# ZATINO_2020.net
KiCad netlist of a schematic drawn in EAGLE
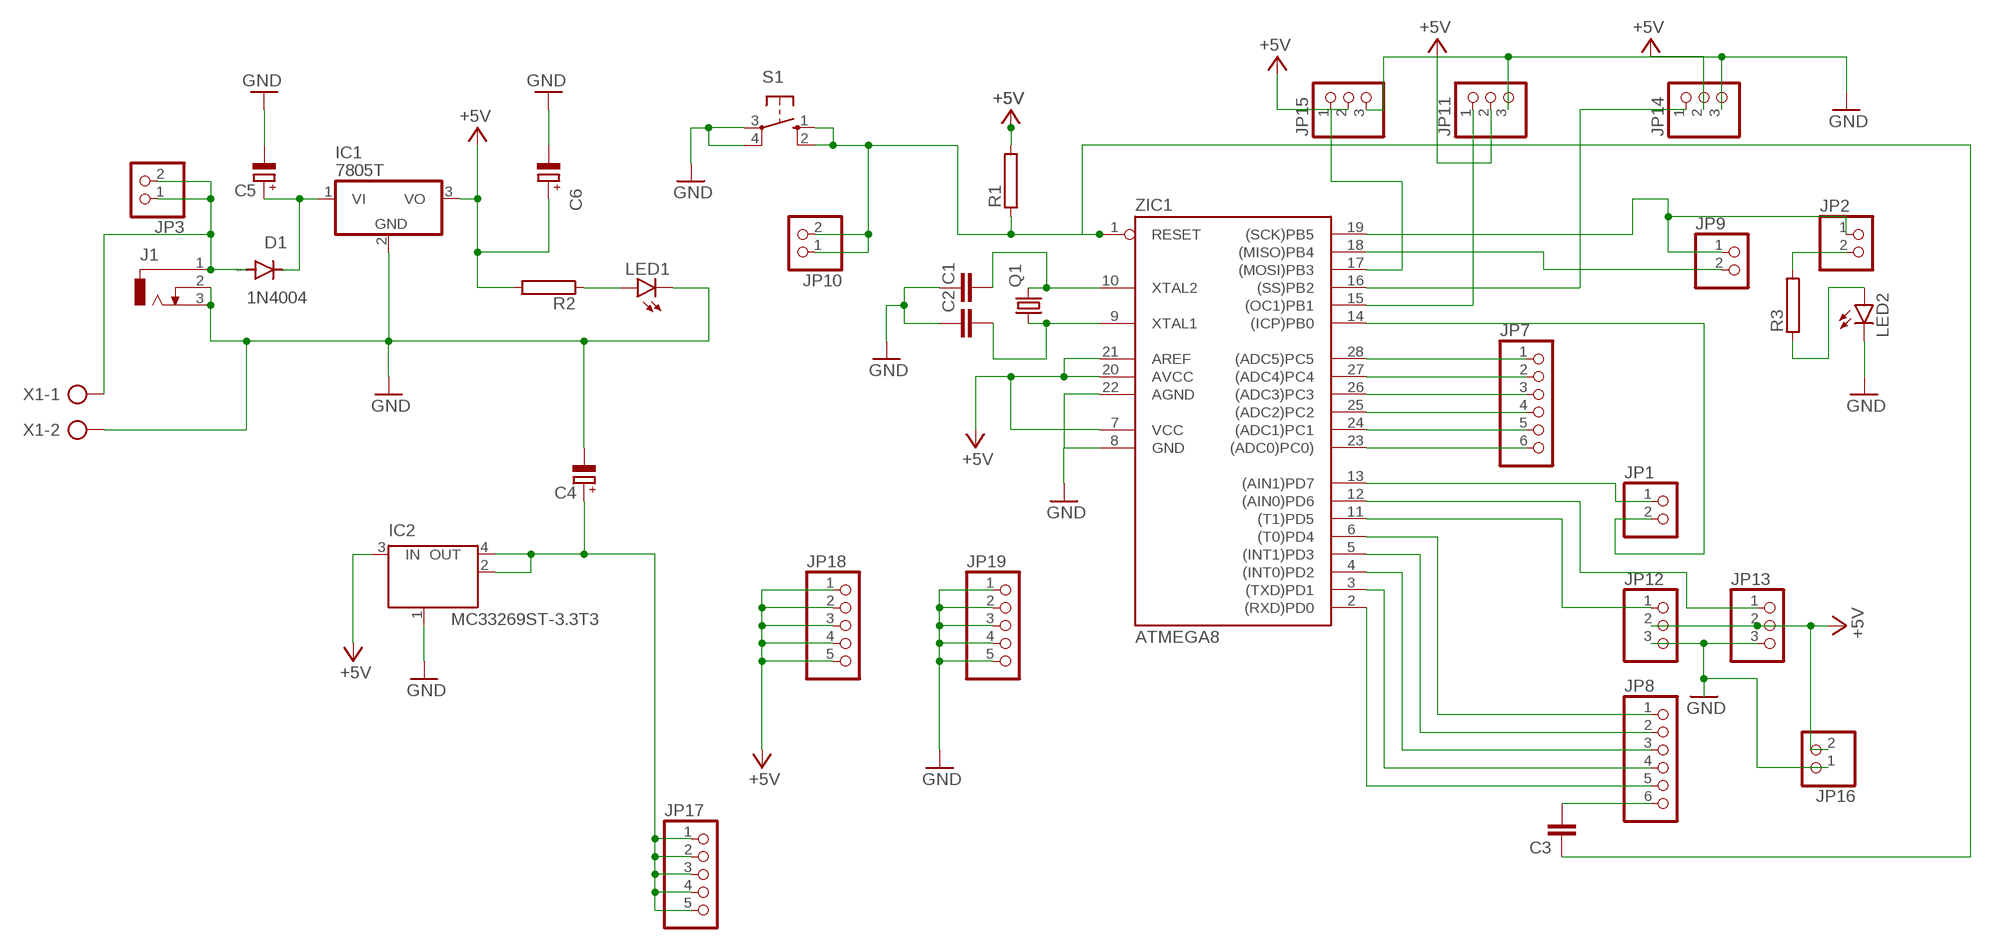
[diagram p0: schematic, sheet 1]

(export (version "E")
  (design (tool "Eeschema 10.0.6"))
  (components
    (comp (ref "C1")
      (value "C2.5/2")
      (footprint "eagle-import:C2.5-2")
      (libsource (lib "eagle-import") (part "C2.5/2"))
    )
    (comp (ref "C2")
      (value "C2.5/2")
      (footprint "eagle-import:C2.5-2")
      (libsource (lib "eagle-import") (part "C2.5/2"))
    )
    (comp (ref "C3")
      (value "C2,5-3")
      (footprint "eagle-import:C2.5-3")
      (libsource (lib "eagle-import") (part "C2,5-3"))
    )
    (comp (ref "C4")
      (value "CPOL-EUE2,5-6E")
      (footprint "eagle-import:E2,5-6E")
      (libsource (lib "eagle-import") (part "CPOL-EUE2,5-6E"))
    )
    (comp (ref "C5")
      (value "CPOL-EUE2,5-6E")
      (footprint "eagle-import:E2,5-6E")
      (libsource (lib "eagle-import") (part "CPOL-EUE2,5-6E"))
    )
    (comp (ref "C6")
      (value "CPOL-EUE2,5-6E")
      (footprint "eagle-import:E2,5-6E")
      (libsource (lib "eagle-import") (part "CPOL-EUE2,5-6E"))
    )
    (comp (ref "D1")
      (value "1N4004")
      (footprint "eagle-import:DO41-10")
      (libsource (lib "eagle-import") (part "1N4004"))
    )
    (comp (ref "IC1")
      (value "7805T")
      (footprint "eagle-import:TO220H")
      (libsource (lib "eagle-import") (part "78T05"))
    )
    (comp (ref "IC2")
      (value "MC33269ST-3.3T3")
      (footprint "eagle-import:SOT223")
      (libsource (lib "eagle-import") (part "MC33269ST-3.3T3"))
    )
    (comp (ref "J1")
      (value "DCJ0303")
      (footprint "eagle-import:DCJ0303")
      (libsource (lib "eagle-import") (part "DCJ0303"))
    )
    (comp (ref "JP1")
      (value "PINHD-1X2")
      (footprint "eagle-import:1X02")
      (libsource (lib "eagle-import") (part "PINHD-1X2"))
    )
    (comp (ref "JP2")
      (value "PINHD-1X2")
      (footprint "eagle-import:1X02")
      (libsource (lib "eagle-import") (part "PINHD-1X2"))
    )
    (comp (ref "JP3")
      (value "PINHD-1X2")
      (footprint "eagle-import:1X02")
      (libsource (lib "eagle-import") (part "PINHD-1X2"))
    )
    (comp (ref "JP7")
      (value "PINHD-1X6")
      (footprint "eagle-import:1X06")
      (libsource (lib "eagle-import") (part "PINHD-1X6"))
    )
    (comp (ref "JP8")
      (value "PINHD-1X6")
      (footprint "eagle-import:1X06")
      (libsource (lib "eagle-import") (part "PINHD-1X6"))
    )
    (comp (ref "JP9")
      (value "PINHD-1X2")
      (footprint "eagle-import:1X02")
      (libsource (lib "eagle-import") (part "PINHD-1X2"))
    )
    (comp (ref "JP10")
      (value "PINHD-1X2")
      (footprint "eagle-import:1X02")
      (libsource (lib "eagle-import") (part "PINHD-1X2"))
    )
    (comp (ref "JP11")
      (value "PINHD-1X3")
      (footprint "eagle-import:1X03")
      (libsource (lib "eagle-import") (part "PINHD-1X3"))
    )
    (comp (ref "JP12")
      (value "PINHD-1X3")
      (footprint "eagle-import:1X03")
      (libsource (lib "eagle-import") (part "PINHD-1X3"))
    )
    (comp (ref "JP13")
      (value "PINHD-1X3")
      (footprint "eagle-import:1X03")
      (libsource (lib "eagle-import") (part "PINHD-1X3"))
    )
    (comp (ref "JP14")
      (value "PINHD-1X3")
      (footprint "eagle-import:1X03")
      (libsource (lib "eagle-import") (part "PINHD-1X3"))
    )
    (comp (ref "JP15")
      (value "PINHD-1X3")
      (footprint "eagle-import:1X03")
      (libsource (lib "eagle-import") (part "PINHD-1X3"))
    )
    (comp (ref "JP16")
      (value "PINHD-1X2")
      (footprint "eagle-import:1X02")
      (libsource (lib "eagle-import") (part "PINHD-1X2"))
    )
    (comp (ref "JP17")
      (value "PINHD-1X5")
      (footprint "eagle-import:1X05")
      (libsource (lib "eagle-import") (part "PINHD-1X5"))
    )
    (comp (ref "JP18")
      (value "PINHD-1X5")
      (footprint "eagle-import:1X05")
      (libsource (lib "eagle-import") (part "PINHD-1X5"))
    )
    (comp (ref "JP19")
      (value "PINHD-1X5")
      (footprint "eagle-import:1X05")
      (libsource (lib "eagle-import") (part "PINHD-1X5"))
    )
    (comp (ref "LED1")
      (value "LED5MM")
      (footprint "eagle-import:LED5MM")
      (libsource (lib "eagle-import") (part "LED5MM"))
    )
    (comp (ref "LED2")
      (value "LED5MM")
      (footprint "eagle-import:LED5MM")
      (libsource (lib "eagle-import") (part "LED5MM"))
    )
    (comp (ref "Q1")
      (value "CRYSTALHC49U-V")
      (footprint "eagle-import:HC49U-V")
      (libsource (lib "eagle-import") (part "CRYSTALHC49U-V"))
    )
    (comp (ref "R1")
      (value "RRS1/4")
      (footprint "eagle-import:RS1_4")
      (fields (field (name "MF") "OHMITE") (field (name "MPN") "RRS1K0"))
      (libsource (lib "eagle-import") (part "RRS1/4"))
    )
    (comp (ref "R2")
      (value "RRS1/4")
      (footprint "eagle-import:RS1_4")
      (fields (field (name "MF") "OHMITE") (field (name "MPN") "RRS1K0"))
      (libsource (lib "eagle-import") (part "RRS1/4"))
    )
    (comp (ref "R3")
      (value "RRS1/4")
      (footprint "eagle-import:RS1_4")
      (fields (field (name "MF") "OHMITE") (field (name "MPN") "RRS1K0"))
      (libsource (lib "eagle-import") (part "RRS1/4"))
    )
    (comp (ref "S1")
      (value "10-XX")
      (footprint "eagle-import:B3F-10XX")
      (fields (field (name "MPN") "B3F-1000"))
      (libsource (lib "eagle-import") (part "10-XX"))
    )
    (comp (ref "X1")
      (value "AK300/2")
      (footprint "eagle-import:AK300_2")
      (libsource (lib "eagle-import") (part "AK300/2"))
    )
    (comp (ref "ZIC1")
      (value "ATMEGA8")
      (footprint "eagle-import:DIL28-3")
      (libsource (lib "eagle-import") (part "AT90S4433P"))
    )
  )
  (nets
    (net (code "1") (name "+5V") (class "Default")
      (node (ref "C6") (pin "+") (pinfunction "+_+") (pintype "passive"))
      (node (ref "IC1") (pin "3") (pinfunction "VO_3") (pintype "passive"))
      (node (ref "IC2") (pin "3") (pinfunction "IN_3") (pintype "input"))
      (node (ref "JP11") (pin "2") (pinfunction "2_2") (pintype "passive"))
      (node (ref "JP12") (pin "2") (pinfunction "2_2") (pintype "passive"))
      (node (ref "JP13") (pin "2") (pinfunction "2_2") (pintype "passive"))
      (node (ref "JP14") (pin "2") (pinfunction "2_2") (pintype "passive"))
      (node (ref "JP15") (pin "2") (pinfunction "2_2") (pintype "passive"))
      (node (ref "JP16") (pin "2") (pinfunction "2_2") (pintype "passive"))
      (node (ref "JP18") (pin "1") (pinfunction "1_1") (pintype "passive"))
      (node (ref "JP18") (pin "2") (pinfunction "2_2") (pintype "passive"))
      (node (ref "JP18") (pin "3") (pinfunction "3_3") (pintype "passive"))
      (node (ref "JP18") (pin "4") (pinfunction "4_4") (pintype "passive"))
      (node (ref "JP18") (pin "5") (pinfunction "5_5") (pintype "passive"))
      (node (ref "R1") (pin "2") (pinfunction "2_2") (pintype "passive"))
      (node (ref "R2") (pin "2") (pinfunction "2_2") (pintype "passive"))
      (node (ref "ZIC1") (pin "20") (pinfunction "AVCC_20") (pintype "power_in"))
      (node (ref "ZIC1") (pin "21") (pinfunction "AREF_21") (pintype "passive"))
      (node (ref "ZIC1") (pin "7") (pinfunction "VCC_7") (pintype "power_in"))
    )
    (net (code "2") (name "GND") (class "Default")
      (node (ref "C1") (pin "1") (pinfunction "1_1") (pintype "passive"))
      (node (ref "C2") (pin "1") (pinfunction "1_1") (pintype "passive"))
      (node (ref "C4") (pin "-") (pinfunction "-_-") (pintype "passive"))
      (node (ref "C5") (pin "-") (pinfunction "-_-") (pintype "passive"))
      (node (ref "C6") (pin "-") (pinfunction "-_-") (pintype "passive"))
      (node (ref "IC1") (pin "2") (pinfunction "GND_2") (pintype "passive"))
      (node (ref "IC2") (pin "1") (pinfunction "GND/ADJ_1") (pintype "input"))
      (node (ref "J1") (pin "2") (pinfunction "2_2") (pintype "passive"))
      (node (ref "J1") (pin "3") (pinfunction "3_3") (pintype "passive"))
      (node (ref "JP11") (pin "3") (pinfunction "3_3") (pintype "passive"))
      (node (ref "JP12") (pin "3") (pinfunction "3_3") (pintype "passive"))
      (node (ref "JP13") (pin "3") (pinfunction "3_3") (pintype "passive"))
      (node (ref "JP14") (pin "3") (pinfunction "3_3") (pintype "passive"))
      (node (ref "JP15") (pin "3") (pinfunction "3_3") (pintype "passive"))
      (node (ref "JP16") (pin "1") (pinfunction "1_1") (pintype "passive"))
      (node (ref "JP19") (pin "1") (pinfunction "1_1") (pintype "passive"))
      (node (ref "JP19") (pin "2") (pinfunction "2_2") (pintype "passive"))
      (node (ref "JP19") (pin "3") (pinfunction "3_3") (pintype "passive"))
      (node (ref "JP19") (pin "4") (pinfunction "4_4") (pintype "passive"))
      (node (ref "JP19") (pin "5") (pinfunction "5_5") (pintype "passive"))
      (node (ref "LED1") (pin "K") (pinfunction "C_K") (pintype "passive"))
      (node (ref "LED2") (pin "K") (pinfunction "C_K") (pintype "passive"))
      (node (ref "S1") (pin "3") (pinfunction "P_3") (pintype "passive"))
      (node (ref "S1") (pin "4") (pinfunction "P1_4") (pintype "passive"))
      (node (ref "X1") (pin "2") (pinfunction "KL_2") (pintype "passive"))
      (node (ref "ZIC1") (pin "22") (pinfunction "AGND_22") (pintype "power_in"))
      (node (ref "ZIC1") (pin "8") (pinfunction "GND_8") (pintype "power_in"))
    )
    (net (code "3") (name "Net-(C3-Pad2)") (class "Default")
      (node (ref "C3") (pin "2") (pinfunction "2_2") (pintype "passive"))
      (node (ref "JP8") (pin "6") (pinfunction "6_6") (pintype "passive"))
    )
    (net (code "4") (name "Net-(C4-Pad+)") (class "Default")
      (node (ref "C4") (pin "+") (pinfunction "+_+") (pintype "passive"))
      (node (ref "IC2") (pin "2") (pinfunction "OUT_2") (pintype "passive"))
      (node (ref "IC2") (pin "4") (pinfunction "OUT_4") (pintype "passive"))
      (node (ref "JP17") (pin "1") (pinfunction "1_1") (pintype "passive"))
      (node (ref "JP17") (pin "2") (pinfunction "2_2") (pintype "passive"))
      (node (ref "JP17") (pin "3") (pinfunction "3_3") (pintype "passive"))
      (node (ref "JP17") (pin "4") (pinfunction "4_4") (pintype "passive"))
      (node (ref "JP17") (pin "5") (pinfunction "5_5") (pintype "passive"))
    )
    (net (code "5") (name "Net-(IC1-VI)") (class "Default")
      (node (ref "C5") (pin "+") (pinfunction "+_+") (pintype "passive"))
      (node (ref "D1") (pin "C") (pinfunction "C_C") (pintype "passive"))
      (node (ref "IC1") (pin "1") (pinfunction "VI_1") (pintype "input"))
    )
    (net (code "6") (name "Net-(JP2-Pad2)") (class "Default")
      (node (ref "JP2") (pin "2") (pinfunction "2_2") (pintype "passive"))
      (node (ref "R3") (pin "2") (pinfunction "2_2") (pintype "passive"))
    )
    (net (code "7") (name "Net-(LED1-PadA)") (class "Default")
      (node (ref "LED1") (pin "A") (pinfunction "A_A") (pintype "passive"))
      (node (ref "R2") (pin "1") (pinfunction "1_1") (pintype "passive"))
    )
    (net (code "8") (name "Net-(LED2-PadA)") (class "Default")
      (node (ref "LED2") (pin "A") (pinfunction "A_A") (pintype "passive"))
      (node (ref "R3") (pin "1") (pinfunction "1_1") (pintype "passive"))
    )
    (net (code "9") (name "Net-(S1-S)") (class "Default")
      (node (ref "C3") (pin "1") (pinfunction "1_1") (pintype "passive"))
      (node (ref "JP10") (pin "1") (pinfunction "1_1") (pintype "passive"))
      (node (ref "JP10") (pin "2") (pinfunction "2_2") (pintype "passive"))
      (node (ref "R1") (pin "1") (pinfunction "1_1") (pintype "passive"))
      (node (ref "S1") (pin "1") (pinfunction "S_1") (pintype "passive"))
      (node (ref "S1") (pin "2") (pinfunction "S1_2") (pintype "passive"))
      (node (ref "ZIC1") (pin "1") (pinfunction "RESET_1") (pintype "input"))
    )
    (net (code "10") (name "Net-(X1A-KL)") (class "Default")
      (node (ref "D1") (pin "A") (pinfunction "A_A") (pintype "passive"))
      (node (ref "J1") (pin "1") (pinfunction "1_1") (pintype "passive"))
      (node (ref "JP3") (pin "1") (pinfunction "1_1") (pintype "passive"))
      (node (ref "JP3") (pin "2") (pinfunction "2_2") (pintype "passive"))
      (node (ref "X1") (pin "1") (pinfunction "KL_1") (pintype "passive"))
    )
    (net (code "11") (name "Net-(ZIC1-(ADC0)PC0))") (class "Default")
      (node (ref "JP7") (pin "6") (pinfunction "6_6") (pintype "passive"))
      (node (ref "ZIC1") (pin "23") (pinfunction "(ADC0)PC0)_23") (pintype "bidirectional"))
    )
    (net (code "12") (name "Net-(ZIC1-(ADC1)PC1)") (class "Default")
      (node (ref "JP7") (pin "5") (pinfunction "5_5") (pintype "passive"))
      (node (ref "ZIC1") (pin "24") (pinfunction "(ADC1)PC1_24") (pintype "bidirectional"))
    )
    (net (code "13") (name "Net-(ZIC1-(ADC2)PC2)") (class "Default")
      (node (ref "JP7") (pin "4") (pinfunction "4_4") (pintype "passive"))
      (node (ref "ZIC1") (pin "25") (pinfunction "(ADC2)PC2_25") (pintype "bidirectional"))
    )
    (net (code "14") (name "Net-(ZIC1-(ADC3)PC3)") (class "Default")
      (node (ref "JP7") (pin "3") (pinfunction "3_3") (pintype "passive"))
      (node (ref "ZIC1") (pin "26") (pinfunction "(ADC3)PC3_26") (pintype "bidirectional"))
    )
    (net (code "15") (name "Net-(ZIC1-(ADC4)PC4)") (class "Default")
      (node (ref "JP7") (pin "2") (pinfunction "2_2") (pintype "passive"))
      (node (ref "ZIC1") (pin "27") (pinfunction "(ADC4)PC4_27") (pintype "bidirectional"))
    )
    (net (code "16") (name "Net-(ZIC1-(ADC5)PC5)") (class "Default")
      (node (ref "JP7") (pin "1") (pinfunction "1_1") (pintype "passive"))
      (node (ref "ZIC1") (pin "28") (pinfunction "(ADC5)PC5_28") (pintype "bidirectional"))
    )
    (net (code "17") (name "Net-(ZIC1-(AIN0)PD6)") (class "Default")
      (node (ref "JP13") (pin "1") (pinfunction "1_1") (pintype "passive"))
      (node (ref "ZIC1") (pin "12") (pinfunction "(AIN0)PD6_12") (pintype "bidirectional"))
    )
    (net (code "18") (name "Net-(ZIC1-(AIN1)PD7)") (class "Default")
      (node (ref "JP1") (pin "1") (pinfunction "1_1") (pintype "passive"))
      (node (ref "ZIC1") (pin "13") (pinfunction "(AIN1)PD7_13") (pintype "bidirectional"))
    )
    (net (code "19") (name "Net-(ZIC1-(ICP)PB0)") (class "Default")
      (node (ref "JP1") (pin "2") (pinfunction "2_2") (pintype "passive"))
      (node (ref "ZIC1") (pin "14") (pinfunction "(ICP)PB0_14") (pintype "bidirectional"))
    )
    (net (code "20") (name "Net-(ZIC1-(INT0)PD2)") (class "Default")
      (node (ref "JP8") (pin "3") (pinfunction "3_3") (pintype "passive"))
      (node (ref "ZIC1") (pin "4") (pinfunction "(INT0)PD2_4") (pintype "bidirectional"))
    )
    (net (code "21") (name "Net-(ZIC1-(INT1)PD3)") (class "Default")
      (node (ref "JP8") (pin "2") (pinfunction "2_2") (pintype "passive"))
      (node (ref "ZIC1") (pin "5") (pinfunction "(INT1)PD3_5") (pintype "bidirectional"))
    )
    (net (code "22") (name "Net-(ZIC1-(MISO)PB4)") (class "Default")
      (node (ref "JP9") (pin "2") (pinfunction "2_2") (pintype "passive"))
      (node (ref "ZIC1") (pin "18") (pinfunction "(MISO)PB4_18") (pintype "bidirectional"))
    )
    (net (code "23") (name "Net-(ZIC1-(MOSI)PB3)") (class "Default")
      (node (ref "JP15") (pin "1") (pinfunction "1_1") (pintype "passive"))
      (node (ref "ZIC1") (pin "17") (pinfunction "(MOSI)PB3_17") (pintype "bidirectional"))
    )
    (net (code "24") (name "Net-(ZIC1-(OC1)PB1)") (class "Default")
      (node (ref "JP11") (pin "1") (pinfunction "1_1") (pintype "passive"))
      (node (ref "ZIC1") (pin "15") (pinfunction "(OC1)PB1_15") (pintype "bidirectional"))
    )
    (net (code "25") (name "Net-(ZIC1-(RXD)PD0)") (class "Default")
      (node (ref "JP8") (pin "5") (pinfunction "5_5") (pintype "passive"))
      (node (ref "ZIC1") (pin "2") (pinfunction "(RXD)PD0_2") (pintype "bidirectional"))
    )
    (net (code "26") (name "Net-(ZIC1-(SCK)PB5)") (class "Default")
      (node (ref "JP2") (pin "1") (pinfunction "1_1") (pintype "passive"))
      (node (ref "JP9") (pin "1") (pinfunction "1_1") (pintype "passive"))
      (node (ref "ZIC1") (pin "19") (pinfunction "(SCK)PB5_19") (pintype "bidirectional"))
    )
    (net (code "27") (name "Net-(ZIC1-(SS)PB2)") (class "Default")
      (node (ref "JP14") (pin "1") (pinfunction "1_1") (pintype "passive"))
      (node (ref "ZIC1") (pin "16") (pinfunction "(SS)PB2_16") (pintype "bidirectional"))
    )
    (net (code "28") (name "Net-(ZIC1-(T0)PD4)") (class "Default")
      (node (ref "JP8") (pin "1") (pinfunction "1_1") (pintype "passive"))
      (node (ref "ZIC1") (pin "6") (pinfunction "(T0)PD4_6") (pintype "bidirectional"))
    )
    (net (code "29") (name "Net-(ZIC1-(T1)PD5)") (class "Default")
      (node (ref "JP12") (pin "1") (pinfunction "1_1") (pintype "passive"))
      (node (ref "ZIC1") (pin "11") (pinfunction "(T1)PD5_11") (pintype "bidirectional"))
    )
    (net (code "30") (name "Net-(ZIC1-(TXD)PD1)") (class "Default")
      (node (ref "JP8") (pin "4") (pinfunction "4_4") (pintype "passive"))
      (node (ref "ZIC1") (pin "3") (pinfunction "(TXD)PD1_3") (pintype "bidirectional"))
    )
    (net (code "31") (name "Net-(ZIC1-XTAL1)") (class "Default")
      (node (ref "C2") (pin "2") (pinfunction "2_2") (pintype "passive"))
      (node (ref "Q1") (pin "1") (pinfunction "1_1") (pintype "passive"))
      (node (ref "ZIC1") (pin "9") (pinfunction "XTAL1_9") (pintype "bidirectional"))
    )
    (net (code "32") (name "Net-(ZIC1-XTAL2)") (class "Default")
      (node (ref "C1") (pin "2") (pinfunction "2_2") (pintype "passive"))
      (node (ref "Q1") (pin "2") (pinfunction "2_2") (pintype "passive"))
      (node (ref "ZIC1") (pin "10") (pinfunction "XTAL2_10") (pintype "bidirectional"))
    )
  )
)
